# RPi-FabScan-HAT_v10.net
KiCad netlist of a schematic drawn in EAGLE
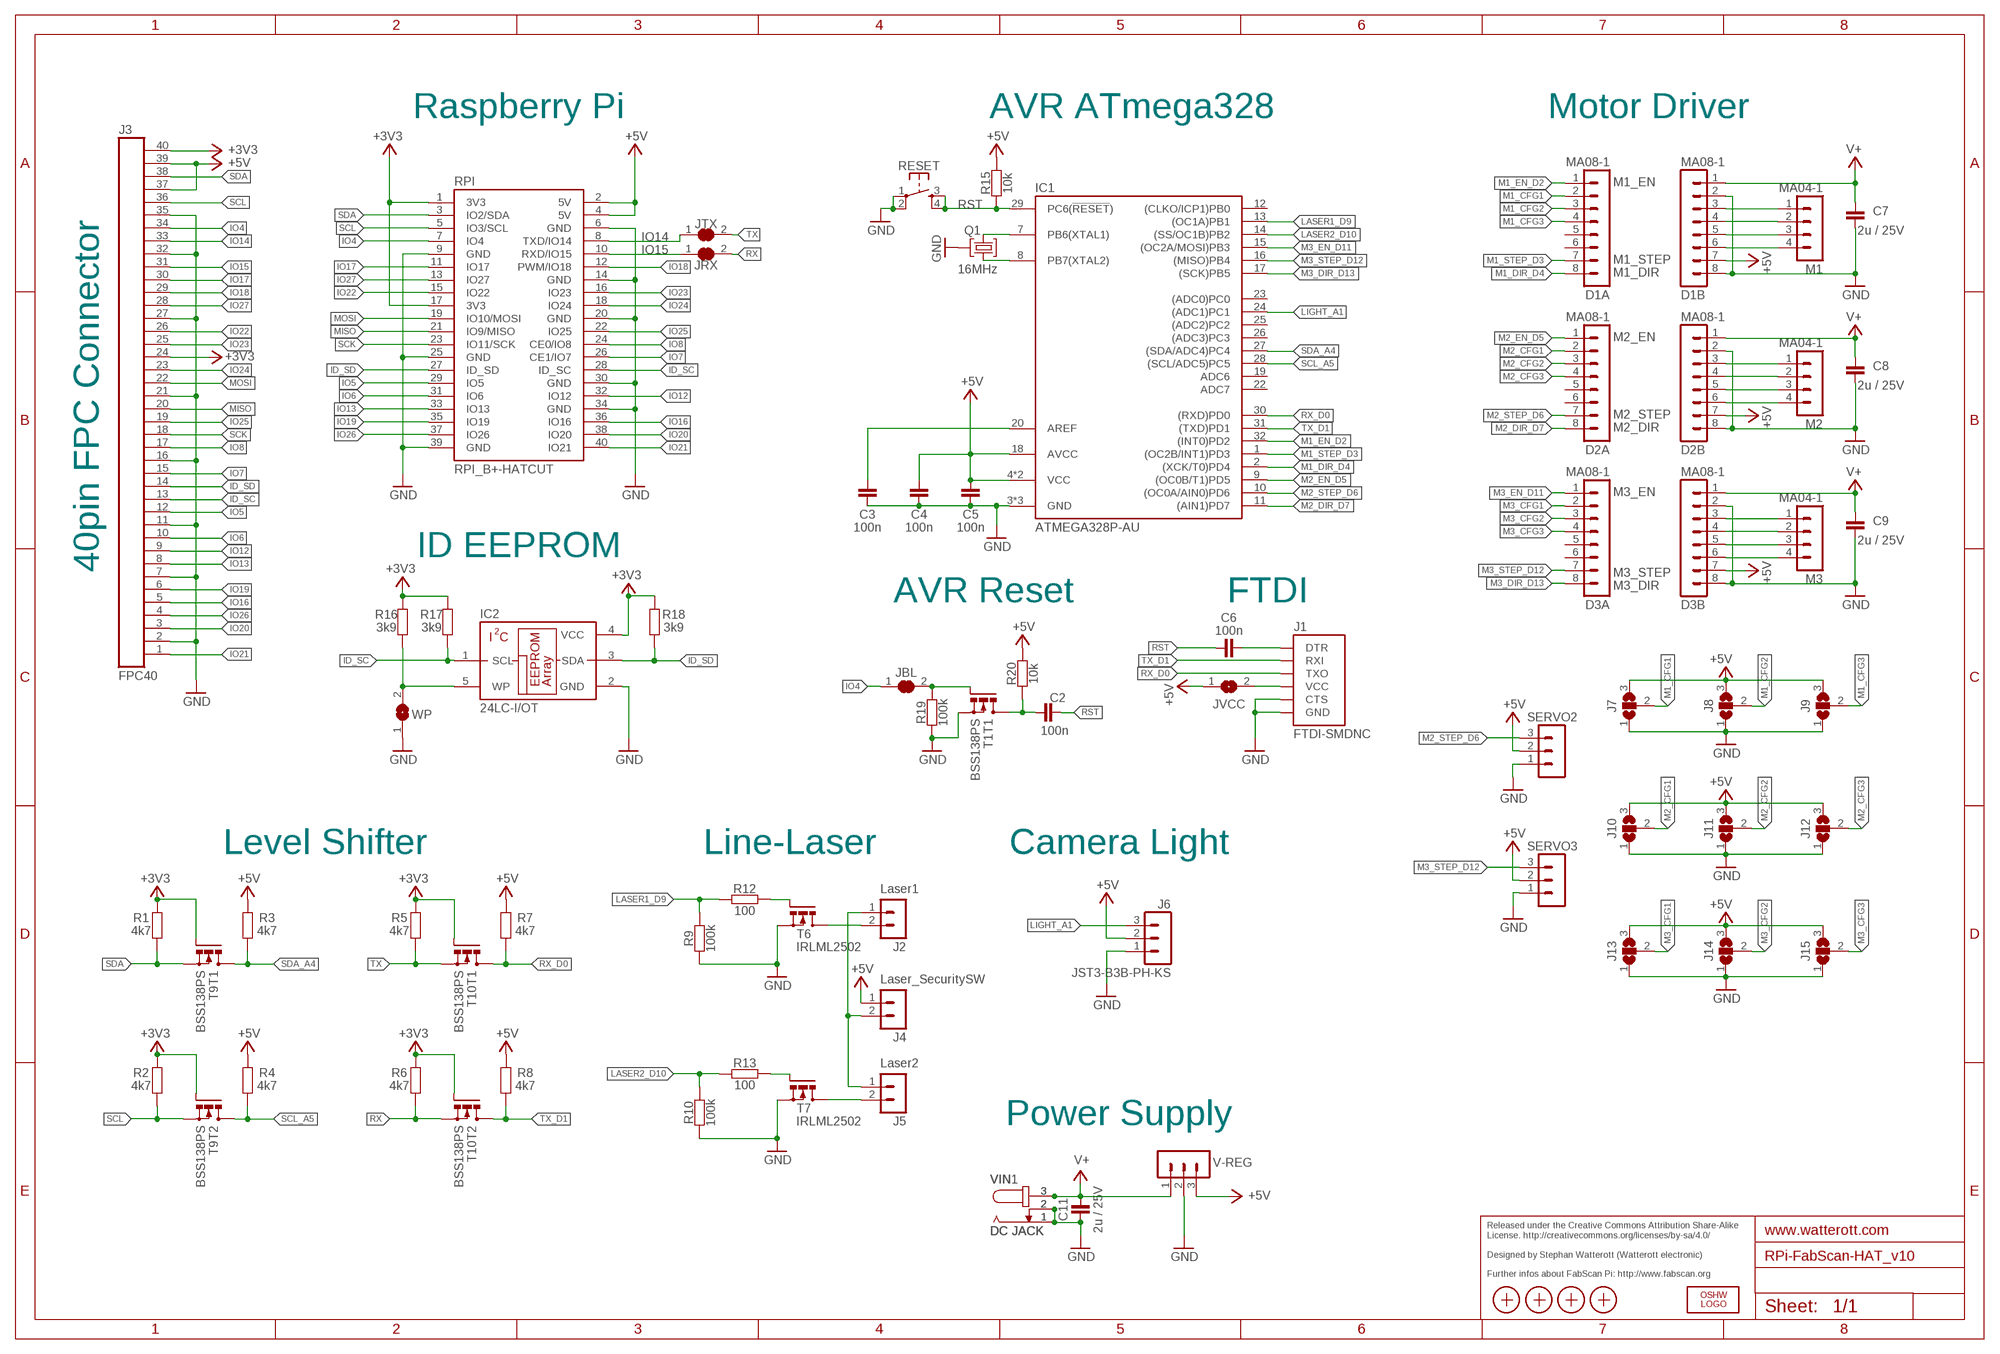
[diagram p0: schematic, sheet 1]

(export (version "E")
  (design (tool "Eeschema 10.0.6"))
  (components
    (comp (ref "1")
      (value "PASSER-07")
      (footprint "eagle-import:PASSER_07MM")
      (libsource (lib "eagle-import") (part "PASSER-07"))
    )
    (comp (ref "2")
      (value "PASSER-07")
      (footprint "eagle-import:PASSER_07MM")
      (libsource (lib "eagle-import") (part "PASSER-07"))
    )
    (comp (ref "C2")
      (value "100n")
      (footprint "eagle-import:C0402")
      (libsource (lib "eagle-import") (part "CAPACITOR-0402"))
    )
    (comp (ref "C3")
      (value "100n")
      (footprint "eagle-import:C0402")
      (libsource (lib "eagle-import") (part "CAPACITOR-0402"))
    )
    (comp (ref "C4")
      (value "100n")
      (footprint "eagle-import:C0402")
      (libsource (lib "eagle-import") (part "CAPACITOR-0402"))
    )
    (comp (ref "C5")
      (value "100n")
      (footprint "eagle-import:C0402")
      (libsource (lib "eagle-import") (part "CAPACITOR-0402"))
    )
    (comp (ref "C6")
      (value "100n")
      (footprint "eagle-import:C0402")
      (libsource (lib "eagle-import") (part "CAPACITOR-0402"))
    )
    (comp (ref "C7")
      (value "2u / 25V")
      (footprint "eagle-import:C1206")
      (libsource (lib "eagle-import") (part "CAPACITOR-1206"))
    )
    (comp (ref "C8")
      (value "2u / 25V")
      (footprint "eagle-import:C1206")
      (libsource (lib "eagle-import") (part "CAPACITOR-1206"))
    )
    (comp (ref "C9")
      (value "2u / 25V")
      (footprint "eagle-import:C1206")
      (libsource (lib "eagle-import") (part "CAPACITOR-1206"))
    )
    (comp (ref "C11")
      (value "2u / 25V")
      (footprint "eagle-import:C1206")
      (libsource (lib "eagle-import") (part "CAPACITOR-1206"))
    )
    (comp (ref "D1A")
      (value "MA08-1")
      (footprint "eagle-import:MA08-1")
      (libsource (lib "eagle-import") (part "MA08-1"))
    )
    (comp (ref "D1B")
      (value "MA08-1")
      (footprint "eagle-import:MA08-1")
      (libsource (lib "eagle-import") (part "MA08-1"))
    )
    (comp (ref "D2A")
      (value "MA08-1")
      (footprint "eagle-import:MA08-1")
      (libsource (lib "eagle-import") (part "MA08-1"))
    )
    (comp (ref "D2B")
      (value "MA08-1")
      (footprint "eagle-import:MA08-1")
      (libsource (lib "eagle-import") (part "MA08-1"))
    )
    (comp (ref "D3A")
      (value "MA08-1")
      (footprint "eagle-import:MA08-1")
      (libsource (lib "eagle-import") (part "MA08-1"))
    )
    (comp (ref "D3B")
      (value "MA08-1")
      (footprint "eagle-import:MA08-1")
      (libsource (lib "eagle-import") (part "MA08-1"))
    )
    (comp (ref "IC1")
      (value "ATMEGA328P-AU")
      (footprint "eagle-import:TQFP32")
      (libsource (lib "eagle-import") (part "ATMEGA328P-AU"))
    )
    (comp (ref "IC2")
      (value "24LC-I/OT")
      (footprint "eagle-import:SOT23-5")
      (libsource (lib "eagle-import") (part "24LC-I/OT"))
    )
    (comp (ref "J1")
      (value "FTDI-SMDNC")
      (footprint "eagle-import:FTDI_SMDNC")
      (libsource (lib "eagle-import") (part "FTDI-SMDNC"))
    )
    (comp (ref "J2")
      (value "Laser1")
      (footprint "eagle-import:MA02-1")
      (libsource (lib "eagle-import") (part "MA02-1"))
    )
    (comp (ref "J3")
      (value "FPC40")
      (footprint "eagle-import:FPC40-0.5")
      (libsource (lib "eagle-import") (part "FPC40"))
    )
    (comp (ref "J4")
      (value "Laser_SecuritySW")
      (footprint "eagle-import:MA02-1")
      (libsource (lib "eagle-import") (part "MA02-1"))
    )
    (comp (ref "J5")
      (value "Laser2")
      (footprint "eagle-import:MA02-1")
      (libsource (lib "eagle-import") (part "MA02-1"))
    )
    (comp (ref "J6")
      (value "JST3-B3B-PH-KS")
      (footprint "eagle-import:JST_B3B-PH-KS")
      (libsource (lib "eagle-import") (part "JST3-B3B-PH-KS"))
    )
    (comp (ref "J7")
      (value "JUMPER3-0603-NC")
      (footprint "eagle-import:JUMPER3-0603_NC")
      (libsource (lib "eagle-import") (part "JUMPER3-0603-NC"))
    )
    (comp (ref "J8")
      (value "JUMPER3-0603-NC")
      (footprint "eagle-import:JUMPER3-0603_NC")
      (libsource (lib "eagle-import") (part "JUMPER3-0603-NC"))
    )
    (comp (ref "J9")
      (value "JUMPER3-0603-NC")
      (footprint "eagle-import:JUMPER3-0603_NC")
      (libsource (lib "eagle-import") (part "JUMPER3-0603-NC"))
    )
    (comp (ref "J10")
      (value "JUMPER3-0603-NC")
      (footprint "eagle-import:JUMPER3-0603_NC")
      (libsource (lib "eagle-import") (part "JUMPER3-0603-NC"))
    )
    (comp (ref "J11")
      (value "JUMPER3-0603-NC")
      (footprint "eagle-import:JUMPER3-0603_NC")
      (libsource (lib "eagle-import") (part "JUMPER3-0603-NC"))
    )
    (comp (ref "J12")
      (value "JUMPER3-0603-NC")
      (footprint "eagle-import:JUMPER3-0603_NC")
      (libsource (lib "eagle-import") (part "JUMPER3-0603-NC"))
    )
    (comp (ref "J13")
      (value "JUMPER3-0603-NC")
      (footprint "eagle-import:JUMPER3-0603_NC")
      (libsource (lib "eagle-import") (part "JUMPER3-0603-NC"))
    )
    (comp (ref "J14")
      (value "JUMPER3-0603-NC")
      (footprint "eagle-import:JUMPER3-0603_NC")
      (libsource (lib "eagle-import") (part "JUMPER3-0603-NC"))
    )
    (comp (ref "J15")
      (value "JUMPER3-0603-NC")
      (footprint "eagle-import:JUMPER3-0603_NC")
      (libsource (lib "eagle-import") (part "JUMPER3-0603-NC"))
    )
    (comp (ref "JBL")
      (value "JUMPER2-0402-NC")
      (footprint "eagle-import:JUMPER2-0402_NC")
      (libsource (lib "eagle-import") (part "JUMPER2-0402-NC"))
    )
    (comp (ref "JRX")
      (value "JUMPER2-0402-NC")
      (footprint "eagle-import:JUMPER2-0402_NC")
      (libsource (lib "eagle-import") (part "JUMPER2-0402-NC"))
    )
    (comp (ref "JTX")
      (value "JUMPER2-0402-NC")
      (footprint "eagle-import:JUMPER2-0402_NC")
      (libsource (lib "eagle-import") (part "JUMPER2-0402-NC"))
    )
    (comp (ref "JVCC")
      (value "JUMPER2-0402-NC")
      (footprint "eagle-import:JUMPER2-0402_NC")
      (libsource (lib "eagle-import") (part "JUMPER2-0402-NC"))
    )
    (comp (ref "LOGO2")
      (value "OSHW_LOGOX0100")
      (footprint "eagle-import:OSHW_6X100")
      (libsource (lib "eagle-import") (part "OSHW_LOGOX0100"))
    )
    (comp (ref "M1")
      (value "MA04-1")
      (footprint "eagle-import:MA04-1")
      (libsource (lib "eagle-import") (part "MA04-1"))
    )
    (comp (ref "M2")
      (value "MA04-1")
      (footprint "eagle-import:MA04-1")
      (libsource (lib "eagle-import") (part "MA04-1"))
    )
    (comp (ref "M3")
      (value "MA04-1")
      (footprint "eagle-import:MA04-1")
      (libsource (lib "eagle-import") (part "MA04-1"))
    )
    (comp (ref "Q1")
      (value "16MHz")
      (footprint "eagle-import:CRYSTAL_32X13")
      (libsource (lib "eagle-import") (part "CRYSTAL-RES-32"))
    )
    (comp (ref "R1")
      (value "4k7")
      (footprint "eagle-import:C0402")
      (libsource (lib "eagle-import") (part "RESISTOR-0402"))
    )
    (comp (ref "R2")
      (value "4k7")
      (footprint "eagle-import:C0402")
      (libsource (lib "eagle-import") (part "RESISTOR-0402"))
    )
    (comp (ref "R3")
      (value "4k7")
      (footprint "eagle-import:C0402")
      (libsource (lib "eagle-import") (part "RESISTOR-0402"))
    )
    (comp (ref "R4")
      (value "4k7")
      (footprint "eagle-import:C0402")
      (libsource (lib "eagle-import") (part "RESISTOR-0402"))
    )
    (comp (ref "R5")
      (value "4k7")
      (footprint "eagle-import:C0402")
      (libsource (lib "eagle-import") (part "RESISTOR-0402"))
    )
    (comp (ref "R6")
      (value "4k7")
      (footprint "eagle-import:C0402")
      (libsource (lib "eagle-import") (part "RESISTOR-0402"))
    )
    (comp (ref "R7")
      (value "4k7")
      (footprint "eagle-import:C0402")
      (libsource (lib "eagle-import") (part "RESISTOR-0402"))
    )
    (comp (ref "R8")
      (value "4k7")
      (footprint "eagle-import:C0402")
      (libsource (lib "eagle-import") (part "RESISTOR-0402"))
    )
    (comp (ref "R9")
      (value "100k")
      (footprint "eagle-import:C0402")
      (libsource (lib "eagle-import") (part "RESISTOR-0402"))
    )
    (comp (ref "R10")
      (value "100k")
      (footprint "eagle-import:C0402")
      (libsource (lib "eagle-import") (part "RESISTOR-0402"))
    )
    (comp (ref "R12")
      (value "100")
      (footprint "eagle-import:C0402")
      (libsource (lib "eagle-import") (part "RESISTOR-0402"))
    )
    (comp (ref "R13")
      (value "100")
      (footprint "eagle-import:C0402")
      (libsource (lib "eagle-import") (part "RESISTOR-0402"))
    )
    (comp (ref "R15")
      (value "10k")
      (footprint "eagle-import:C0402")
      (libsource (lib "eagle-import") (part "RESISTOR-0402"))
    )
    (comp (ref "R16")
      (value "3k9")
      (footprint "eagle-import:C0402")
      (libsource (lib "eagle-import") (part "RESISTOR-0402"))
    )
    (comp (ref "R17")
      (value "3k9")
      (footprint "eagle-import:C0402")
      (libsource (lib "eagle-import") (part "RESISTOR-0402"))
    )
    (comp (ref "R18")
      (value "3k9")
      (footprint "eagle-import:C0402")
      (libsource (lib "eagle-import") (part "RESISTOR-0402"))
    )
    (comp (ref "R19")
      (value "100k")
      (footprint "eagle-import:C0402")
      (libsource (lib "eagle-import") (part "RESISTOR-0402"))
    )
    (comp (ref "R20")
      (value "10k")
      (footprint "eagle-import:C0402")
      (libsource (lib "eagle-import") (part "RESISTOR-0402"))
    )
    (comp (ref "RESET")
      (value "SW-TACTILE-PTS840P")
      (footprint "eagle-import:SW_PTS840P")
      (libsource (lib "eagle-import") (part "SW-TACTILE-PTS840P"))
    )
    (comp (ref "RPI")
      (value "RPI_B+-HATCUT")
      (footprint "eagle-import:RPI-B+HAT_CUTOUT")
      (libsource (lib "eagle-import") (part "RPI_B+-HATCUT"))
    )
    (comp (ref "SERVO2")
      (value "MA03-1")
      (footprint "eagle-import:MA03-1")
      (libsource (lib "eagle-import") (part "MA03-1"))
    )
    (comp (ref "SERVO3")
      (value "MA03-1")
      (footprint "eagle-import:MA03-1")
      (libsource (lib "eagle-import") (part "MA03-1"))
    )
    (comp (ref "T1")
      (value "BSS138PS")
      (footprint "eagle-import:SOT363")
      (libsource (lib "eagle-import") (part "BSS138PS"))
    )
    (comp (ref "T6")
      (value "IRLML2502")
      (footprint "eagle-import:SOT23")
      (libsource (lib "eagle-import") (part "MOSFET-N-SOT23"))
    )
    (comp (ref "T7")
      (value "IRLML2502")
      (footprint "eagle-import:SOT23")
      (libsource (lib "eagle-import") (part "MOSFET-N-SOT23"))
    )
    (comp (ref "T9")
      (value "BSS138PS")
      (footprint "eagle-import:SOT363")
      (libsource (lib "eagle-import") (part "BSS138PS"))
    )
    (comp (ref "T10")
      (value "BSS138PS")
      (footprint "eagle-import:SOT363")
      (libsource (lib "eagle-import") (part "BSS138PS"))
    )
    (comp (ref "V-REG")
      (value "MA03-1")
      (footprint "eagle-import:MA03-1")
      (libsource (lib "eagle-import") (part "MA03-1"))
    )
    (comp (ref "VIN")
      (value "DC JACK")
      (footprint "eagle-import:DC-JACK")
      (libsource (lib "eagle-import") (part "DC-JACK-2.1"))
    )
    (comp (ref "VIN1")
      (value "DC JACK")
      (footprint "eagle-import:DC-JACK")
      (libsource (lib "eagle-import") (part "DC-JACK-2.1"))
    )
    (comp (ref "WP")
      (value "JUMPER2-0402-NC")
      (footprint "eagle-import:JUMPER2-0402_NC")
      (libsource (lib "eagle-import") (part "JUMPER2-0402-NC"))
    )
    (comp (ref "X1")
      (value "PASSER-07")
      (footprint "eagle-import:PASSER_07MM")
      (libsource (lib "eagle-import") (part "PASSER-07"))
    )
    (comp (ref "X4")
      (value "PASSER-07")
      (footprint "eagle-import:PASSER_07MM")
      (libsource (lib "eagle-import") (part "PASSER-07"))
    )
  )
  (nets
    (net (code "1") (name "+3V3") (class "Default")
      (node (ref "IC2") (pin "4") (pinfunction "VCC_4") (pintype "power_in"))
      (node (ref "J3") (pin "24") (pinfunction "24_24") (pintype "passive"))
      (node (ref "J3") (pin "40") (pinfunction "40_40") (pintype "passive"))
      (node (ref "R1") (pin "1") (pinfunction "1_1") (pintype "passive"))
      (node (ref "R16") (pin "2") (pinfunction "2_2") (pintype "passive"))
      (node (ref "R17") (pin "2") (pinfunction "2_2") (pintype "passive"))
      (node (ref "R18") (pin "2") (pinfunction "2_2") (pintype "passive"))
      (node (ref "R2") (pin "1") (pinfunction "1_1") (pintype "passive"))
      (node (ref "R5") (pin "1") (pinfunction "1_1") (pintype "passive"))
      (node (ref "R6") (pin "1") (pinfunction "1_1") (pintype "passive"))
      (node (ref "RPI") (pin "1") (pinfunction "3V3_1") (pintype "passive"))
      (node (ref "RPI") (pin "17") (pinfunction "3V3_17") (pintype "passive"))
      (node (ref "T10") (pin "2") (pinfunction "G_2") (pintype "passive"))
      (node (ref "T10") (pin "5") (pinfunction "G_5") (pintype "passive"))
      (node (ref "T9") (pin "2") (pinfunction "G_2") (pintype "passive"))
      (node (ref "T9") (pin "5") (pinfunction "G_5") (pintype "passive"))
    )
    (net (code "2") (name "+5V") (class "Default")
      (node (ref "C4") (pin "2") (pinfunction "2_2") (pintype "passive"))
      (node (ref "C5") (pin "2") (pinfunction "2_2") (pintype "passive"))
      (node (ref "D1B") (pin "7") (pinfunction "7_7") (pintype "passive"))
      (node (ref "D2B") (pin "7") (pinfunction "7_7") (pintype "passive"))
      (node (ref "D3B") (pin "7") (pinfunction "7_7") (pintype "passive"))
      (node (ref "IC1") (pin "18") (pinfunction "AVCC_18") (pintype "power_in"))
      (node (ref "IC1") (pin "4") (pinfunction "VCC_4") (pintype "power_in"))
      (node (ref "IC1") (pin "6") (pinfunction "VCC_6") (pintype "power_in"))
      (node (ref "J10") (pin "3") (pinfunction "3_3") (pintype "passive"))
      (node (ref "J11") (pin "3") (pinfunction "3_3") (pintype "passive"))
      (node (ref "J12") (pin "3") (pinfunction "3_3") (pintype "passive"))
      (node (ref "J13") (pin "3") (pinfunction "3_3") (pintype "passive"))
      (node (ref "J14") (pin "3") (pinfunction "3_3") (pintype "passive"))
      (node (ref "J15") (pin "3") (pinfunction "3_3") (pintype "passive"))
      (node (ref "J3") (pin "37") (pinfunction "37_37") (pintype "passive"))
      (node (ref "J3") (pin "39") (pinfunction "39_39") (pintype "passive"))
      (node (ref "J4") (pin "1") (pinfunction "1_1") (pintype "passive"))
      (node (ref "J6") (pin "2") (pinfunction "2_2") (pintype "passive"))
      (node (ref "J7") (pin "3") (pinfunction "3_3") (pintype "passive"))
      (node (ref "J8") (pin "3") (pinfunction "3_3") (pintype "passive"))
      (node (ref "J9") (pin "3") (pinfunction "3_3") (pintype "passive"))
      (node (ref "JVCC") (pin "1") (pinfunction "1_1") (pintype "passive"))
      (node (ref "R15") (pin "2") (pinfunction "2_2") (pintype "passive"))
      (node (ref "R20") (pin "2") (pinfunction "2_2") (pintype "passive"))
      (node (ref "R3") (pin "1") (pinfunction "1_1") (pintype "passive"))
      (node (ref "R4") (pin "1") (pinfunction "1_1") (pintype "passive"))
      (node (ref "R7") (pin "1") (pinfunction "1_1") (pintype "passive"))
      (node (ref "R8") (pin "1") (pinfunction "1_1") (pintype "passive"))
      (node (ref "RPI") (pin "2") (pinfunction "5V_2") (pintype "passive"))
      (node (ref "RPI") (pin "4") (pinfunction "5V_4") (pintype "passive"))
      (node (ref "SERVO2") (pin "2") (pinfunction "2_2") (pintype "passive"))
      (node (ref "SERVO3") (pin "2") (pinfunction "2_2") (pintype "passive"))
      (node (ref "V-REG") (pin "3") (pinfunction "3_3") (pintype "passive"))
    )
    (net (code "3") (name "GND") (class "Default")
      (node (ref "C11") (pin "1") (pinfunction "1_1") (pintype "passive"))
      (node (ref "C3") (pin "1") (pinfunction "1_1") (pintype "passive"))
      (node (ref "C4") (pin "1") (pinfunction "1_1") (pintype "passive"))
      (node (ref "C5") (pin "1") (pinfunction "1_1") (pintype "passive"))
      (node (ref "C7") (pin "1") (pinfunction "1_1") (pintype "passive"))
      (node (ref "C8") (pin "1") (pinfunction "1_1") (pintype "passive"))
      (node (ref "C9") (pin "1") (pinfunction "1_1") (pintype "passive"))
      (node (ref "D1B") (pin "2") (pinfunction "2_2") (pintype "passive"))
      (node (ref "D1B") (pin "8") (pinfunction "8_8") (pintype "passive"))
      (node (ref "D2B") (pin "2") (pinfunction "2_2") (pintype "passive"))
      (node (ref "D2B") (pin "8") (pinfunction "8_8") (pintype "passive"))
      (node (ref "D3B") (pin "2") (pinfunction "2_2") (pintype "passive"))
      (node (ref "D3B") (pin "8") (pinfunction "8_8") (pintype "passive"))
      (node (ref "IC1") (pin "21") (pinfunction "GND_21") (pintype "power_in"))
      (node (ref "IC1") (pin "3") (pinfunction "GND_3") (pintype "power_in"))
      (node (ref "IC1") (pin "5") (pinfunction "GND_5") (pintype "power_in"))
      (node (ref "IC2") (pin "2") (pinfunction "GND_2") (pintype "power_in"))
      (node (ref "J1") (pin "1-GND") (pinfunction "GND_1-GND") (pintype "power_in"))
      (node (ref "J1") (pin "2-CTS") (pinfunction "CTS_2-CTS") (pintype "bidirectional"))
      (node (ref "J10") (pin "1") (pinfunction "1_1") (pintype "passive"))
      (node (ref "J11") (pin "1") (pinfunction "1_1") (pintype "passive"))
      (node (ref "J12") (pin "1") (pinfunction "1_1") (pintype "passive"))
      (node (ref "J13") (pin "1") (pinfunction "1_1") (pintype "passive"))
      (node (ref "J14") (pin "1") (pinfunction "1_1") (pintype "passive"))
      (node (ref "J15") (pin "1") (pinfunction "1_1") (pintype "passive"))
      (node (ref "J3") (pin "11") (pinfunction "11_11") (pintype "passive"))
      (node (ref "J3") (pin "16") (pinfunction "16_16") (pintype "passive"))
      (node (ref "J3") (pin "2") (pinfunction "2_2") (pintype "passive"))
      (node (ref "J3") (pin "21") (pinfunction "21_21") (pintype "passive"))
      (node (ref "J3") (pin "27") (pinfunction "27_27") (pintype "passive"))
      (node (ref "J3") (pin "32") (pinfunction "32_32") (pintype "passive"))
      (node (ref "J3") (pin "35") (pinfunction "35_35") (pintype "passive"))
      (node (ref "J3") (pin "7") (pinfunction "7_7") (pintype "passive"))
      (node (ref "J6") (pin "1") (pinfunction "1_1") (pintype "passive"))
      (node (ref "J7") (pin "1") (pinfunction "1_1") (pintype "passive"))
      (node (ref "J8") (pin "1") (pinfunction "1_1") (pintype "passive"))
      (node (ref "J9") (pin "1") (pinfunction "1_1") (pintype "passive"))
      (node (ref "Q1") (pin "GND") (pinfunction "GND_GND") (pintype "passive"))
      (node (ref "R10") (pin "1") (pinfunction "1_1") (pintype "passive"))
      (node (ref "R19") (pin "1") (pinfunction "1_1") (pintype "passive"))
      (node (ref "R9") (pin "1") (pinfunction "1_1") (pintype "passive"))
      (node (ref "RESET") (pin "1") (pinfunction "P1_1") (pintype "passive"))
      (node (ref "RESET") (pin "2") (pinfunction "P2_2") (pintype "passive"))
      (node (ref "RPI") (pin "14") (pinfunction "GND_14") (pintype "passive"))
      (node (ref "RPI") (pin "20") (pinfunction "GND_20") (pintype "passive"))
      (node (ref "RPI") (pin "25") (pinfunction "GND_25") (pintype "passive"))
      (node (ref "RPI") (pin "30") (pinfunction "GND_30") (pintype "bidirectional"))
      (node (ref "RPI") (pin "34") (pinfunction "GND_34") (pintype "bidirectional"))
      (node (ref "RPI") (pin "39") (pinfunction "GND_39") (pintype "bidirectional"))
      (node (ref "RPI") (pin "6") (pinfunction "GND_6") (pintype "passive"))
      (node (ref "RPI") (pin "9") (pinfunction "GND_9") (pintype "passive"))
      (node (ref "SERVO2") (pin "1") (pinfunction "1_1") (pintype "passive"))
      (node (ref "SERVO3") (pin "1") (pinfunction "1_1") (pintype "passive"))
      (node (ref "T1") (pin "1") (pinfunction "S_1") (pintype "passive"))
      (node (ref "T6") (pin "2") (pinfunction "S_2") (pintype "passive"))
      (node (ref "T7") (pin "2") (pinfunction "S_2") (pintype "passive"))
      (node (ref "V-REG") (pin "2") (pinfunction "2_2") (pintype "passive"))
      (node (ref "VIN") (pin "1") (pinfunction "1_1") (pintype "passive"))
      (node (ref "VIN") (pin "2") (pinfunction "2_2") (pintype "passive"))
      (node (ref "VIN1") (pin "1") (pinfunction "1_1") (pintype "passive"))
      (node (ref "VIN1") (pin "2") (pinfunction "2_2") (pintype "passive"))
      (node (ref "WP") (pin "1") (pinfunction "1_1") (pintype "passive"))
    )
    (net (code "4") (name "ID_SC") (class "Default")
      (node (ref "IC2") (pin "1") (pinfunction "SCL_1") (pintype "bidirectional"))
      (node (ref "J3") (pin "13") (pinfunction "13_13") (pintype "passive"))
      (node (ref "R17") (pin "1") (pinfunction "1_1") (pintype "passive"))
      (node (ref "RPI") (pin "28") (pinfunction "ID_SC_28") (pintype "bidirectional"))
    )
    (net (code "5") (name "ID_SD") (class "Default")
      (node (ref "IC2") (pin "3") (pinfunction "SDA_3") (pintype "bidirectional"))
      (node (ref "J3") (pin "14") (pinfunction "14_14") (pintype "passive"))
      (node (ref "R18") (pin "1") (pinfunction "1_1") (pintype "passive"))
      (node (ref "RPI") (pin "27") (pinfunction "ID_SD_27") (pintype "bidirectional"))
    )
    (net (code "6") (name "IO4") (class "Default")
      (node (ref "J3") (pin "34") (pinfunction "34_34") (pintype "passive"))
      (node (ref "JBL") (pin "1") (pinfunction "1_1") (pintype "passive"))
      (node (ref "RPI") (pin "7") (pinfunction "IO4_7") (pintype "passive"))
    )
    (net (code "7") (name "IO5") (class "Default")
      (node (ref "J3") (pin "12") (pinfunction "12_12") (pintype "passive"))
      (node (ref "RPI") (pin "29") (pinfunction "IO5_29") (pintype "bidirectional"))
    )
    (net (code "8") (name "IO6") (class "Default")
      (node (ref "J3") (pin "10") (pinfunction "10_10") (pintype "passive"))
      (node (ref "RPI") (pin "31") (pinfunction "IO6_31") (pintype "bidirectional"))
    )
    (net (code "9") (name "IO7") (class "Default")
      (node (ref "J3") (pin "15") (pinfunction "15_15") (pintype "passive"))
      (node (ref "RPI") (pin "26") (pinfunction "CE1/IO7_26") (pintype "passive"))
    )
    (net (code "10") (name "IO8") (class "Default")
      (node (ref "J3") (pin "17") (pinfunction "17_17") (pintype "passive"))
      (node (ref "RPI") (pin "24") (pinfunction "CE0/IO8_24") (pintype "passive"))
    )
    (net (code "11") (name "IO12") (class "Default")
      (node (ref "J3") (pin "9") (pinfunction "9_9") (pintype "passive"))
      (node (ref "RPI") (pin "32") (pinfunction "IO12_32") (pintype "bidirectional"))
    )
    (net (code "12") (name "IO13") (class "Default")
      (node (ref "J3") (pin "8") (pinfunction "8_8") (pintype "passive"))
      (node (ref "RPI") (pin "33") (pinfunction "IO13_33") (pintype "bidirectional"))
    )
    (net (code "13") (name "IO14") (class "Default")
      (node (ref "J3") (pin "33") (pinfunction "33_33") (pintype "passive"))
      (node (ref "JTX") (pin "1") (pinfunction "1_1") (pintype "passive"))
      (node (ref "RPI") (pin "8") (pinfunction "TXD/IO14_8") (pintype "passive"))
    )
    (net (code "14") (name "IO15") (class "Default")
      (node (ref "J3") (pin "31") (pinfunction "31_31") (pintype "passive"))
      (node (ref "JRX") (pin "1") (pinfunction "1_1") (pintype "passive"))
      (node (ref "RPI") (pin "10") (pinfunction "RXD/IO15_10") (pintype "passive"))
    )
    (net (code "15") (name "IO16") (class "Default")
      (node (ref "J3") (pin "5") (pinfunction "5_5") (pintype "passive"))
      (node (ref "RPI") (pin "36") (pinfunction "IO16_36") (pintype "bidirectional"))
    )
    (net (code "16") (name "IO17") (class "Default")
      (node (ref "J3") (pin "30") (pinfunction "30_30") (pintype "passive"))
      (node (ref "RPI") (pin "11") (pinfunction "IO17_11") (pintype "passive"))
    )
    (net (code "17") (name "IO18") (class "Default")
      (node (ref "J3") (pin "29") (pinfunction "29_29") (pintype "passive"))
      (node (ref "RPI") (pin "12") (pinfunction "PWM/IO18_12") (pintype "passive"))
    )
    (net (code "18") (name "IO19") (class "Default")
      (node (ref "J3") (pin "6") (pinfunction "6_6") (pintype "passive"))
      (node (ref "RPI") (pin "35") (pinfunction "IO19_35") (pintype "bidirectional"))
    )
    (net (code "19") (name "IO20") (class "Default")
      (node (ref "J3") (pin "3") (pinfunction "3_3") (pintype "passive"))
      (node (ref "RPI") (pin "38") (pinfunction "IO20_38") (pintype "bidirectional"))
    )
    (net (code "20") (name "IO21") (class "Default")
      (node (ref "J3") (pin "1") (pinfunction "1_1") (pintype "passive"))
      (node (ref "RPI") (pin "40") (pinfunction "IO21_40") (pintype "bidirectional"))
    )
    (net (code "21") (name "IO22") (class "Default")
      (node (ref "J3") (pin "26") (pinfunction "26_26") (pintype "passive"))
      (node (ref "RPI") (pin "15") (pinfunction "IO22_15") (pintype "passive"))
    )
    (net (code "22") (name "IO23") (class "Default")
      (node (ref "J3") (pin "25") (pinfunction "25_25") (pintype "passive"))
      (node (ref "RPI") (pin "16") (pinfunction "IO23_16") (pintype "passive"))
    )
    (net (code "23") (name "IO24") (class "Default")
      (node (ref "J3") (pin "23") (pinfunction "23_23") (pintype "passive"))
      (node (ref "RPI") (pin "18") (pinfunction "IO24_18") (pintype "passive"))
    )
    (net (code "24") (name "IO25") (class "Default")
      (node (ref "J3") (pin "19") (pinfunction "19_19") (pintype "passive"))
      (node (ref "RPI") (pin "22") (pinfunction "IO25_22") (pintype "passive"))
    )
    (net (code "25") (name "IO26") (class "Default")
      (node (ref "J3") (pin "4") (pinfunction "4_4") (pintype "passive"))
      (node (ref "RPI") (pin "37") (pinfunction "IO26_37") (pintype "bidirectional"))
    )
    (net (code "26") (name "IO27") (class "Default")
      (node (ref "J3") (pin "28") (pinfunction "28_28") (pintype "passive"))
      (node (ref "RPI") (pin "13") (pinfunction "IO27_13") (pintype "passive"))
    )
    (net (code "27") (name "LASER1_D9") (class "Default")
      (node (ref "IC1") (pin "13") (pinfunction "(OC1A)PB1_13") (pintype "bidirectional"))
      (node (ref "R12") (pin "1") (pinfunction "1_1") (pintype "passive"))
      (node (ref "R9") (pin "2") (pinfunction "2_2") (pintype "passive"))
    )
    (net (code "28") (name "LASER2_D10") (class "Default")
      (node (ref "IC1") (pin "14") (pinfunction "(SS/OC1B)PB2_14") (pintype "bidirectional"))
      (node (ref "R10") (pin "2") (pinfunction "2_2") (pintype "passive"))
      (node (ref "R13") (pin "1") (pinfunction "1_1") (pintype "passive"))
    )
    (net (code "29") (name "LIGHT_A1") (class "Default")
      (node (ref "IC1") (pin "24") (pinfunction "(ADC1)PC1_24") (pintype "bidirectional"))
      (node (ref "J6") (pin "3") (pinfunction "3_3") (pintype "passive"))
    )
    (net (code "30") (name "M1_CFG1") (class "Default")
      (node (ref "D1A") (pin "2") (pinfunction "2_2") (pintype "passive"))
      (node (ref "J7") (pin "2") (pinfunction "2_2") (pintype "passive"))
    )
    (net (code "31") (name "M1_CFG2") (class "Default")
      (node (ref "D1A") (pin "3") (pinfunction "3_3") (pintype "passive"))
      (node (ref "J8") (pin "2") (pinfunction "2_2") (pintype "passive"))
    )
    (net (code "32") (name "M1_CFG3") (class "Default")
      (node (ref "D1A") (pin "4") (pinfunction "4_4") (pintype "passive"))
      (node (ref "J9") (pin "2") (pinfunction "2_2") (pintype "passive"))
    )
    (net (code "33") (name "M1_DIR_D4") (class "Default")
      (node (ref "D1A") (pin "8") (pinfunction "8_8") (pintype "passive"))
      (node (ref "IC1") (pin "2") (pinfunction "(XCK/T0)PD4_2") (pintype "bidirectional"))
    )
    (net (code "34") (name "M1_EN_D2") (class "Default")
      (node (ref "D1A") (pin "1") (pinfunction "1_1") (pintype "passive"))
      (node (ref "IC1") (pin "32") (pinfunction "(INT0)PD2_32") (pintype "bidirectional"))
    )
    (net (code "35") (name "M1_STEP_D3") (class "Default")
      (node (ref "D1A") (pin "7") (pinfunction "7_7") (pintype "passive"))
      (node (ref "IC1") (pin "1") (pinfunction "(OC2B/INT1)PD3_1") (pintype "bidirectional"))
    )
    (net (code "36") (name "M2_CFG1") (class "Default")
      (node (ref "D2A") (pin "2") (pinfunction "2_2") (pintype "passive"))
      (node (ref "J10") (pin "2") (pinfunction "2_2") (pintype "passive"))
    )
    (net (code "37") (name "M2_CFG2") (class "Default")
      (node (ref "D2A") (pin "3") (pinfunction "3_3") (pintype "passive"))
      (node (ref "J11") (pin "2") (pinfunction "2_2") (pintype "passive"))
    )
    (net (code "38") (name "M2_CFG3") (class "Default")
      (node (ref "D2A") (pin "4") (pinfunction "4_4") (pintype "passive"))
      (node (ref "J12") (pin "2") (pinfunction "2_2") (pintype "passive"))
    )
    (net (code "39") (name "M2_DIR_D7") (class "Default")
      (node (ref "D2A") (pin "8") (pinfunction "8_8") (pintype "passive"))
      (node (ref "IC1") (pin "11") (pinfunction "(AIN1)PD7_11") (pintype "bidirectional"))
    )
    (net (code "40") (name "M2_EN_D5") (class "Default")
      (node (ref "D2A") (pin "1") (pinfunction "1_1") (pintype "passive"))
      (node (ref "IC1") (pin "9") (pinfunction "(OC0B/T1)PD5_9") (pintype "bidirectional"))
    )
    (net (code "41") (name "M2_STEP_D6") (class "Default")
      (node (ref "D2A") (pin "7") (pinfunction "7_7") (pintype "passive"))
      (node (ref "IC1") (pin "10") (pinfunction "(OC0A/AIN0)PD6_10") (pintype "bidirectional"))
      (node (ref "SERVO2") (pin "3") (pinfunction "3_3") (pintype "passive"))
    )
    (net (code "42") (name "M3_CFG1") (class "Default")
      (node (ref "D3A") (pin "2") (pinfunction "2_2") (pintype "passive"))
      (node (ref "J13") (pin "2") (pinfunction "2_2") (pintype "passive"))
    )
    (net (code "43") (name "M3_CFG2") (class "Default")
      (node (ref "D3A") (pin "3") (pinfunction "3_3") (pintype "passive"))
      (node (ref "J14") (pin "2") (pinfunction "2_2") (pintype "passive"))
    )
    (net (code "44") (name "M3_CFG3") (class "Default")
      (node (ref "D3A") (pin "4") (pinfunction "4_4") (pintype "passive"))
      (node (ref "J15") (pin "2") (pinfunction "2_2") (pintype "passive"))
    )
    (net (code "45") (name "M3_DIR_D13") (class "Default")
      (node (ref "D3A") (pin "8") (pinfunction "8_8") (pintype "passive"))
      (node (ref "IC1") (pin "17") (pinfunction "(SCK)PB5_17") (pintype "bidirectional"))
    )
    (net (code "46") (name "M3_EN_D11") (class "Default")
      (node (ref "D3A") (pin "1") (pinfunction "1_1") (pintype "passive"))
      (node (ref "IC1") (pin "15") (pinfunction "(OC2A/MOSI)PB3_15") (pintype "bidirectional"))
    )
    (net (code "47") (name "M3_STEP_D12") (class "Default")
      (node (ref "D3A") (pin "7") (pinfunction "7_7") (pintype "passive"))
      (node (ref "IC1") (pin "16") (pinfunction "(MISO)PB4_16") (pintype "bidirectional"))
      (node (ref "SERVO3") (pin "3") (pinfunction "3_3") (pintype "passive"))
    )
    (net (code "48") (name "MISO") (class "Default")
      (node (ref "J3") (pin "20") (pinfunction "20_20") (pintype "passive"))
      (node (ref "RPI") (pin "21") (pinfunction "IO9/MISO_21") (pintype "passive"))
    )
    (net (code "49") (name "MOSI") (class "Default")
      (node (ref "J3") (pin "22") (pinfunction "22_22") (pintype "passive"))
      (node (ref "RPI") (pin "19") (pinfunction "IO10/MOSI_19") (pintype "passive"))
    )
    (net (code "50") (name "Net-(D1B-Pad3)") (class "Default")
      (node (ref "D1B") (pin "3") (pinfunction "3_3") (pintype "passive"))
      (node (ref "M1") (pin "1") (pinfunction "1_1") (pintype "passive"))
    )
    (net (code "51") (name "Net-(D1B-Pad4)") (class "Default")
      (node (ref "D1B") (pin "4") (pinfunction "4_4") (pintype "passive"))
      (node (ref "M1") (pin "2") (pinfunction "2_2") (pintype "passive"))
    )
    (net (code "52") (name "Net-(D1B-Pad5)") (class "Default")
      (node (ref "D1B") (pin "5") (pinfunction "5_5") (pintype "passive"))
      (node (ref "M1") (pin "3") (pinfunction "3_3") (pintype "passive"))
    )
    (net (code "53") (name "Net-(D1B-Pad6)") (class "Default")
      (node (ref "D1B") (pin "6") (pinfunction "6_6") (pintype "passive"))
      (node (ref "M1") (pin "4") (pinfunction "4_4") (pintype "passive"))
    )
    (net (code "54") (name "Net-(D2B-Pad3)") (class "Default")
      (node (ref "D2B") (pin "3") (pinfunction "3_3") (pintype "passive"))
      (node (ref "M2") (pin "1") (pinfunction "1_1") (pintype "passive"))
    )
    (net (code "55") (name "Net-(D2B-Pad4)") (class "Default")
      (node (ref "D2B") (pin "4") (pinfunction "4_4") (pintype "passive"))
      (node (ref "M2") (pin "2") (pinfunction "2_2") (pintype "passive"))
    )
    (net (code "56") (name "Net-(D2B-Pad5)") (class "Default")
      (node (ref "D2B") (pin "5") (pinfunction "5_5") (pintype "passive"))
      (node (ref "M2") (pin "3") (pinfunction "3_3") (pintype "passive"))
    )
    (net (code "57") (name "Net-(D2B-Pad6)") (class "Default")
      (node (ref "D2B") (pin "6") (pinfunction "6_6") (pintype "passive"))
      (node (ref "M2") (pin "4") (pinfunction "4_4") (pintype "passive"))
    )
    (net (code "58") (name "Net-(D3B-Pad3)") (class "Default")
      (node (ref "D3B") (pin "3") (pinfunction "3_3") (pintype "passive"))
      (node (ref "M3") (pin "1") (pinfunction "1_1") (pintype "passive"))
    )
    (net (code "59") (name "Net-(D3B-Pad4)") (class "Default")
      (node (ref "D3B") (pin "4") (pinfunction "4_4") (pintype "passive"))
      (node (ref "M3") (pin "2") (pinfunction "2_2") (pintype "passive"))
    )
    (net (code "60") (name "Net-(D3B-Pad5)") (class "Default")
      (node (ref "D3B") (pin "5") (pinfunction "5_5") (pintype "passive"))
      (node (ref "M3") (pin "3") (pinfunction "3_3") (pintype "passive"))
    )
    (net (code "61") (name "Net-(D3B-Pad6)") (class "Default")
      (node (ref "D3B") (pin "6") (pinfunction "6_6") (pintype "passive"))
      (node (ref "M3") (pin "4") (pinfunction "4_4") (pintype "passive"))
    )
    (net (code "62") (name "Net-(IC1-AREF)") (class "Default")
      (node (ref "C3") (pin "2") (pinfunction "2_2") (pintype "passive"))
      (node (ref "IC1") (pin "20") (pinfunction "AREF_20") (pintype "passive"))
    )
    (net (code "63") (name "Net-(IC1-PB6(XTAL1))") (class "Default")
      (node (ref "IC1") (pin "7") (pinfunction "PB6(XTAL1)_7") (pintype "bidirectional"))
      (node (ref "Q1") (pin "2") (pinfunction "2_2") (pintype "passive"))
    )
    (net (code "64") (name "Net-(IC1-PB7(XTAL2))") (class "Default")
      (node (ref "IC1") (pin "8") (pinfunction "PB7(XTAL2)_8") (pintype "bidirectional"))
      (node (ref "Q1") (pin "1") (pinfunction "1_1") (pintype "passive"))
    )
    (net (code "65") (name "Net-(IC2-WP)") (class "Default")
      (node (ref "IC2") (pin "5") (pinfunction "WP_5") (pintype "bidirectional"))
      (node (ref "R16") (pin "1") (pinfunction "1_1") (pintype "passive"))
      (node (ref "WP") (pin "2") (pinfunction "2_2") (pintype "passive"))
    )
    (net (code "66") (name "Net-(J1-DTR)") (class "Default")
      (node (ref "C6") (pin "1") (pinfunction "1_1") (pintype "passive"))
      (node (ref "J1") (pin "6-DTR") (pinfunction "DTR_6-DTR") (pintype "bidirectional"))
    )
    (net (code "67") (name "Net-(J1-VCC)") (class "Default")
      (node (ref "J1") (pin "3-VCC") (pinfunction "VCC_3-VCC") (pintype "power_in"))
      (node (ref "JVCC") (pin "2") (pinfunction "2_2") (pintype "passive"))
    )
    (net (code "68") (name "Net-(J2-Pad1)") (class "Default")
      (node (ref "J2") (pin "1") (pinfunction "1_1") (pintype "passive"))
      (node (ref "J4") (pin "2") (pinfunction "2_2") (pintype "passive"))
      (node (ref "J5") (pin "1") (pinfunction "1_1") (pintype "passive"))
    )
    (net (code "69") (name "Net-(T1A-D)") (class "Default")
      (node (ref "C2") (pin "2") (pinfunction "2_2") (pintype "passive"))
      (node (ref "R20") (pin "1") (pinfunction "1_1") (pintype "passive"))
      (node (ref "T1") (pin "6") (pinfunction "D_6") (pintype "passive"))
    )
    (net (code "70") (name "Net-(T1A-G)") (class "Default")
      (node (ref "JBL") (pin "2") (pinfunction "2_2") (pintype "passive"))
      (node (ref "R19") (pin "2") (pinfunction "2_2") (pintype "passive"))
      (node (ref "T1") (pin "2") (pinfunction "G_2") (pintype "passive"))
    )
    (net (code "71") (name "Net-(T6-D)") (class "Default")
      (node (ref "J2") (pin "2") (pinfunction "2_2") (pintype "passive"))
      (node (ref "T6") (pin "3") (pinfunction "D_3") (pintype "passive"))
    )
    (net (code "72") (name "Net-(T6-G)") (class "Default")
      (node (ref "R12") (pin "2") (pinfunction "2_2") (pintype "passive"))
      (node (ref "T6") (pin "1") (pinfunction "G_1") (pintype "passive"))
    )
    (net (code "73") (name "Net-(T7-D)") (class "Default")
      (node (ref "J5") (pin "2") (pinfunction "2_2") (pintype "passive"))
      (node (ref "T7") (pin "3") (pinfunction "D_3") (pintype "passive"))
    )
    (net (code "74") (name "Net-(T7-G)") (class "Default")
      (node (ref "R13") (pin "2") (pinfunction "2_2") (pintype "passive"))
      (node (ref "T7") (pin "1") (pinfunction "G_1") (pintype "passive"))
    )
    (net (code "75") (name "RST") (class "Default")
      (node (ref "C2") (pin "1") (pinfunction "1_1") (pintype "passive"))
      (node (ref "C6") (pin "2") (pinfunction "2_2") (pintype "passive"))
      (node (ref "IC1") (pin "29") (pinfunction "PC6(~{RESET})_29") (pintype "bidirectional"))
      (node (ref "R15") (pin "1") (pinfunction "1_1") (pintype "passive"))
      (node (ref "RESET") (pin "3") (pinfunction "S1_3") (pintype "passive"))
      (node (ref "RESET") (pin "4") (pinfunction "S2_4") (pintype "passive"))
    )
    (net (code "76") (name "RX") (class "Default")
      (node (ref "JRX") (pin "2") (pinfunction "2_2") (pintype "passive"))
      (node (ref "R6") (pin "2") (pinfunction "2_2") (pintype "passive"))
      (node (ref "T10") (pin "4") (pinfunction "S_4") (pintype "passive"))
    )
    (net (code "77") (name "RX_D0") (class "Default")
      (node (ref "IC1") (pin "30") (pinfunction "(RXD)PD0_30") (pintype "bidirectional"))
      (node (ref "J1") (pin "4-TXO") (pinfunction "TXO_4-TXO") (pintype "bidirectional"))
      (node (ref "R7") (pin "2") (pinfunction "2_2") (pintype "passive"))
      (node (ref "T10") (pin "6") (pinfunction "D_6") (pintype "passive"))
    )
    (net (code "78") (name "SCK") (class "Default")
      (node (ref "J3") (pin "18") (pinfunction "18_18") (pintype "passive"))
      (node (ref "RPI") (pin "23") (pinfunction "IO11/SCK_23") (pintype "passive"))
    )
    (net (code "79") (name "SCL") (class "Default")
      (node (ref "J3") (pin "36") (pinfunction "36_36") (pintype "passive"))
      (node (ref "R2") (pin "2") (pinfunction "2_2") (pintype "passive"))
      (node (ref "RPI") (pin "5") (pinfunction "IO3/SCL_5") (pintype "passive"))
      (node (ref "T9") (pin "4") (pinfunction "S_4") (pintype "passive"))
    )
    (net (code "80") (name "SCL_A5") (class "Default")
      (node (ref "IC1") (pin "28") (pinfunction "(SCL/ADC5)PC5_28") (pintype "bidirectional"))
      (node (ref "R4") (pin "2") (pinfunction "2_2") (pintype "passive"))
      (node (ref "T9") (pin "3") (pinfunction "D_3") (pintype "passive"))
    )
    (net (code "81") (name "SDA") (class "Default")
      (node (ref "J3") (pin "38") (pinfunction "38_38") (pintype "passive"))
      (node (ref "R1") (pin "2") (pinfunction "2_2") (pintype "passive"))
      (node (ref "RPI") (pin "3") (pinfunction "IO2/SDA_3") (pintype "passive"))
      (node (ref "T9") (pin "1") (pinfunction "S_1") (pintype "passive"))
    )
    (net (code "82") (name "SDA_A4") (class "Default")
      (node (ref "IC1") (pin "27") (pinfunction "(SDA/ADC4)PC4_27") (pintype "bidirectional"))
      (node (ref "R3") (pin "2") (pinfunction "2_2") (pintype "passive"))
      (node (ref "T9") (pin "6") (pinfunction "D_6") (pintype "passive"))
    )
    (net (code "83") (name "TX") (class "Default")
      (node (ref "JTX") (pin "2") (pinfunction "2_2") (pintype "passive"))
      (node (ref "R5") (pin "2") (pinfunction "2_2") (pintype "passive"))
      (node (ref "T10") (pin "1") (pinfunction "S_1") (pintype "passive"))
    )
    (net (code "84") (name "TX_D1") (class "Default")
      (node (ref "IC1") (pin "31") (pinfunction "(TXD)PD1_31") (pintype "bidirectional"))
      (node (ref "J1") (pin "5-RXI") (pinfunction "RXI_5-RXI") (pintype "bidirectional"))
      (node (ref "R8") (pin "2") (pinfunction "2_2") (pintype "passive"))
      (node (ref "T10") (pin "3") (pinfunction "D_3") (pintype "passive"))
    )
    (net (code "85") (name "V+") (class "Default")
      (node (ref "C11") (pin "2") (pinfunction "2_2") (pintype "passive"))
      (node (ref "C7") (pin "2") (pinfunction "2_2") (pintype "passive"))
      (node (ref "C8") (pin "2") (pinfunction "2_2") (pintype "passive"))
      (node (ref "C9") (pin "2") (pinfunction "2_2") (pintype "passive"))
      (node (ref "D1B") (pin "1") (pinfunction "1_1") (pintype "passive"))
      (node (ref "D2B") (pin "1") (pinfunction "1_1") (pintype "passive"))
      (node (ref "D3B") (pin "1") (pinfunction "1_1") (pintype "passive"))
      (node (ref "V-REG") (pin "1") (pinfunction "1_1") (pintype "passive"))
      (node (ref "VIN") (pin "3") (pinfunction "3_3") (pintype "passive"))
      (node (ref "VIN1") (pin "3") (pinfunction "3_3") (pintype "passive"))
    )
    (net (code "86") (name "unconnected-(D1A-Pad5)") (class "Default")
      (node (ref "D1A") (pin "5") (pinfunction "5_5") (pintype "passive"))
    )
    (net (code "87") (name "unconnected-(D1A-Pad6)") (class "Default")
      (node (ref "D1A") (pin "6") (pinfunction "6_6") (pintype "passive"))
    )
    (net (code "88") (name "unconnected-(D2A-Pad5)") (class "Default")
      (node (ref "D2A") (pin "5") (pinfunction "5_5") (pintype "passive"))
    )
    (net (code "89") (name "unconnected-(D2A-Pad6)") (class "Default")
      (node (ref "D2A") (pin "6") (pinfunction "6_6") (pintype "passive"))
    )
    (net (code "90") (name "unconnected-(D3A-Pad5)") (class "Default")
      (node (ref "D3A") (pin "5") (pinfunction "5_5") (pintype "passive"))
    )
    (net (code "91") (name "unconnected-(D3A-Pad6)") (class "Default")
      (node (ref "D3A") (pin "6") (pinfunction "6_6") (pintype "passive"))
    )
    (net (code "92") (name "unconnected-(IC1-(ADC0)PC0-Pad23)") (class "Default")
      (node (ref "IC1") (pin "23") (pinfunction "(ADC0)PC0_23") (pintype "bidirectional"))
    )
    (net (code "93") (name "unconnected-(IC1-(ADC2)PC2-Pad25)") (class "Default")
      (node (ref "IC1") (pin "25") (pinfunction "(ADC2)PC2_25") (pintype "bidirectional"))
    )
    (net (code "94") (name "unconnected-(IC1-(ADC3)PC3-Pad26)") (class "Default")
      (node (ref "IC1") (pin "26") (pinfunction "(ADC3)PC3_26") (pintype "bidirectional"))
    )
    (net (code "95") (name "unconnected-(IC1-(CLKO{slash}ICP1)PB0-Pad12)") (class "Default")
      (node (ref "IC1") (pin "12") (pinfunction "(CLKO/ICP1)PB0_12") (pintype "bidirectional"))
    )
    (net (code "96") (name "unconnected-(IC1-ADC6-Pad19)") (class "Default")
      (node (ref "IC1") (pin "19") (pinfunction "ADC6_19") (pintype "bidirectional"))
    )
    (net (code "97") (name "unconnected-(IC1-ADC7-Pad22)") (class "Default")
      (node (ref "IC1") (pin "22") (pinfunction "ADC7_22") (pintype "bidirectional"))
    )
  )
)
